# Schematic_Sensors.net
KiCad netlist of a schematic drawn in Altium Designer
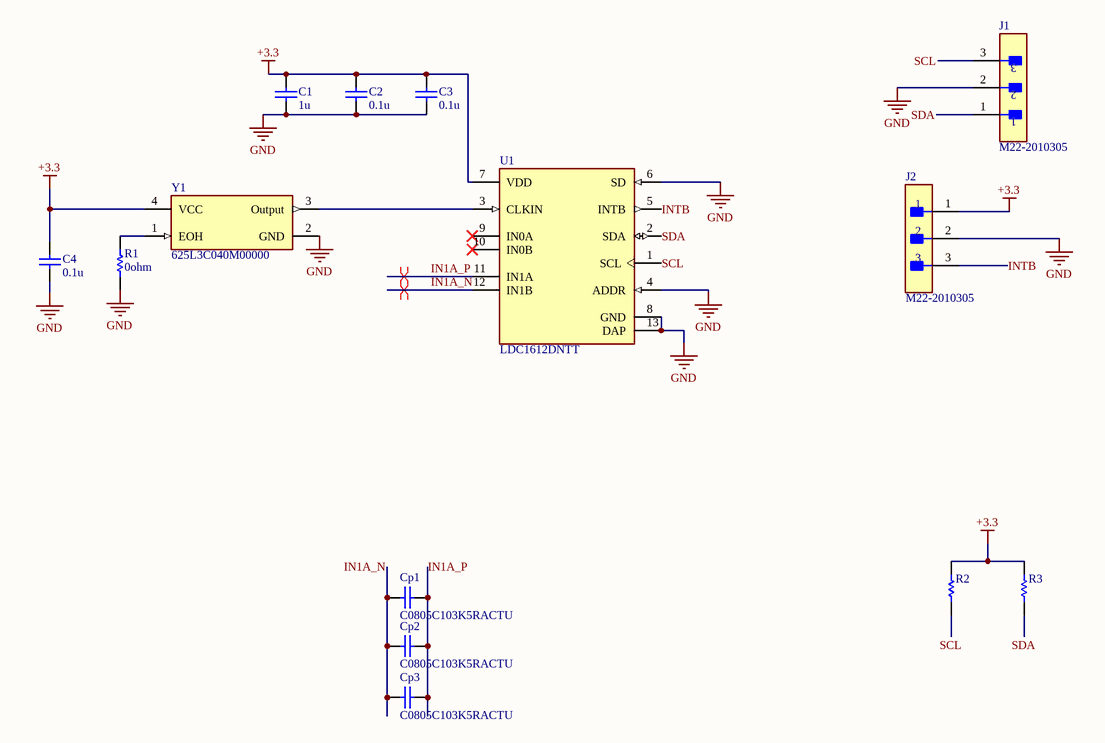
[diagram p0: Schematic_Sensors.SchDoc]

(export (version "E")
  (design (tool "Eeschema 10.0.6"))
  (components
    (comp (ref "C1")
      (value "1u")
      (footprint "CAPC1608X90X35ML10T15")
      (description "Chip Capacitor, 22 pF, +/- 5%, 50 V, -55 to 125 degC, 0603 (1608 Metric), RoHS, Tape and Reel")
      (fields (field (name "MANUFACTURER") "Murata"))
      (libsource (lib "Altium Content Vault") (part "CAP-NP-2"))
    )
    (comp (ref "C2")
      (value "0.1u")
      (footprint "CAPC1608X90X35ML10T15")
      (description "Chip Capacitor, 22 pF, +/- 5%, 50 V, -55 to 125 degC, 0603 (1608 Metric), RoHS, Tape and Reel")
      (fields (field (name "MANUFACTURER") "Murata"))
      (libsource (lib "Altium Content Vault") (part "CAP-NP-2"))
    )
    (comp (ref "C3")
      (value "0.1u")
      (footprint "CAPC1608X90X35ML10T15")
      (description "Chip Capacitor, 22 pF, +/- 5%, 50 V, -55 to 125 degC, 0603 (1608 Metric), RoHS, Tape and Reel")
      (fields (field (name "MANUFACTURER") "Murata"))
      (libsource (lib "Altium Content Vault") (part "CAP-NP-2"))
    )
    (comp (ref "C4")
      (value "0.1u")
      (footprint "CAPC1608X90X35ML10T15")
      (description "Chip Capacitor, 22 pF, +/- 5%, 50 V, -55 to 125 degC, 0603 (1608 Metric), RoHS, Tape and Reel")
      (fields (field (name "MANUFACTURER") "Murata"))
      (libsource (lib "Altium Content Vault") (part "CAP-NP-2"))
    )
    (comp (ref "Cp1")
      (value "C0805C103K5RACTU")
      (footprint "CAPC2013X88X50LL20T25")
      (fields (field (name "MANUFACTURER") "Kemet"))
      (libsource (lib "Altium Content Vault") (part "CAP"))
    )
    (comp (ref "Cp2")
      (value "C0805C103K5RACTU")
      (footprint "CAPC2013X88X50LL20T25")
      (fields (field (name "MANUFACTURER") "Kemet"))
      (libsource (lib "Altium Content Vault") (part "CAP"))
    )
    (comp (ref "Cp3")
      (value "C0805C103K5RACTU")
      (footprint "CAPC2013X88X50LL20T25")
      (fields (field (name "MANUFACTURER") "Kemet"))
      (libsource (lib "Altium Content Vault") (part "CAP"))
    )
    (comp (ref "J1")
      (value "M22-2010305")
      (footprint "FP-M22-2010305-MFG")
      (description "CONN HEADER VERT 3POS 2MM")
      (libsource (lib "") (part "d6a96a410146d2d686cfe982f2af7ec_1"))
    )
    (comp (ref "J2")
      (value "M22-2010305")
      (footprint "FP-M22-2010305-MFG")
      (description "CONN HEADER VERT 3POS 2MM")
      (libsource (lib "Altium Content Vault") (part "d6a96a410146d2d686cfe982f2af7ec"))
    )
    (comp (ref "R1")
      (value "0ohm")
      (footprint "RESC1608X55X25ML10T15")
      (description "Chip Resistor, 0 Ohm, +/- 5%, 0.1 W, -55 to 155 degC, 0603 (1608 Metric), RoHS, Tape and Reel")
      (fields (field (name "TOLERANCE") "5%") (field (name "MANUFACTURER") "Yageo"))
      (libsource (lib "Altium Content Vault") (part "RES-2"))
    )
    (comp (ref "R2")
      (value "CRCW060310K0FKEA")
      (footprint "RESC1609X50X30NL8T20")
      (description "Chip Resistor, 10 KOhm, +/- 1%, 100 mW, -55 to 155 degC, 0603 (1608 Metric), RoHS, Tape and Reel")
      (fields (field (name "MANUFACTURER") "Vishay Semiconductor"))
      (libsource (lib "Altium Content Vault") (part "RES-2"))
    )
    (comp (ref "R3")
      (value "CRCW060310K0FKEA")
      (footprint "RESC1609X50X30NL8T20")
      (description "Chip Resistor, 10 KOhm, +/- 1%, 100 mW, -55 to 155 degC, 0603 (1608 Metric), RoHS, Tape and Reel")
      (fields (field (name "MANUFACTURER") "Vishay Semiconductor"))
      (libsource (lib "Altium Content Vault") (part "RES-2"))
    )
    (comp (ref "U1")
      (value "LDC1612DNTT")
      (footprint "FP-DNT0012B-MFG")
      (description "IC IND TO DGTL 28BIT 1K 12WSON")
      (libsource (lib "Altium Content Vault") (part "d15d1dde6957b5eef4a1a46d84eb5d6"))
    )
    (comp (ref "Y1")
      (value "625L3C040M00000")
      (footprint "FP-625-MFG")
      (description "XTAL OSC XO 40.0000MHZ CMOS SMD")
      (libsource (lib "Altium Content Vault") (part "9c3e14d6329513fa8fa4cc4a840e5d2"))
    )
  )
  (nets
    (net (code "1") (name "+3.3") (class "Default")
      (node (ref "C1") (pin "2") (pinfunction "2_2") (pintype "passive"))
      (node (ref "C2") (pin "2") (pinfunction "2_2") (pintype "passive"))
      (node (ref "C3") (pin "2") (pinfunction "2_2") (pintype "passive"))
      (node (ref "C4") (pin "2") (pinfunction "2_2") (pintype "passive"))
      (node (ref "J2") (pin "1") (pinfunction "1_1") (pintype "passive"))
      (node (ref "R2") (pin "2") (pinfunction "2_2") (pintype "passive"))
      (node (ref "R3") (pin "2") (pinfunction "2_2") (pintype "passive"))
      (node (ref "U1") (pin "7") (pinfunction "VDD_7") (pintype "power_in"))
      (node (ref "Y1") (pin "4") (pinfunction "VCC_4") (pintype "power_in"))
    )
    (net (code "2") (name "/IN1A_N") (class "Default")
      (node (ref "Cp1") (pin "1") (pinfunction "1_1") (pintype "passive"))
      (node (ref "Cp2") (pin "1") (pinfunction "1_1") (pintype "passive"))
      (node (ref "Cp3") (pin "1") (pinfunction "1_1") (pintype "passive"))
      (node (ref "U1") (pin "12") (pinfunction "IN1B_12") (pintype "passive"))
    )
    (net (code "3") (name "/IN1A_P") (class "Default")
      (node (ref "Cp1") (pin "2") (pinfunction "2_2") (pintype "passive"))
      (node (ref "Cp2") (pin "2") (pinfunction "2_2") (pintype "passive"))
      (node (ref "Cp3") (pin "2") (pinfunction "2_2") (pintype "passive"))
      (node (ref "U1") (pin "11") (pinfunction "IN1A_11") (pintype "passive"))
    )
    (net (code "4") (name "/INTB") (class "Default")
      (node (ref "J2") (pin "3") (pinfunction "3_3") (pintype "passive"))
      (node (ref "U1") (pin "5") (pinfunction "INTB_5") (pintype "output"))
    )
    (net (code "5") (name "/SCL") (class "Default")
      (node (ref "J1") (pin "3") (pinfunction "3_3") (pintype "passive"))
      (node (ref "R2") (pin "1") (pinfunction "1_1") (pintype "passive"))
      (node (ref "U1") (pin "1") (pinfunction "SCL_1") (pintype "passive"))
    )
    (net (code "6") (name "/SDA") (class "Default")
      (node (ref "J1") (pin "1") (pinfunction "1_1") (pintype "passive"))
      (node (ref "R3") (pin "1") (pinfunction "1_1") (pintype "passive"))
      (node (ref "U1") (pin "2") (pinfunction "SDA_2") (pintype "bidirectional"))
    )
    (net (code "7") (name "GND") (class "Default")
      (node (ref "C1") (pin "1") (pinfunction "1_1") (pintype "passive"))
      (node (ref "C2") (pin "1") (pinfunction "1_1") (pintype "passive"))
      (node (ref "C3") (pin "1") (pinfunction "1_1") (pintype "passive"))
      (node (ref "C4") (pin "1") (pinfunction "1_1") (pintype "passive"))
      (node (ref "J1") (pin "2") (pinfunction "2_2") (pintype "passive"))
      (node (ref "J2") (pin "2") (pinfunction "2_2") (pintype "passive"))
      (node (ref "R1") (pin "1") (pinfunction "1_1") (pintype "passive"))
      (node (ref "U1") (pin "13") (pinfunction "DAP_13") (pintype "power_in"))
      (node (ref "U1") (pin "4") (pinfunction "ADDR_4") (pintype "input"))
      (node (ref "U1") (pin "6") (pinfunction "SD_6") (pintype "input"))
      (node (ref "U1") (pin "8") (pinfunction "GND_8") (pintype "power_in"))
      (node (ref "Y1") (pin "2") (pinfunction "GND_2") (pintype "power_in"))
    )
    (net (code "8") (name "Net-(U1-CLKIN)") (class "Default")
      (node (ref "U1") (pin "3") (pinfunction "CLKIN_3") (pintype "input"))
      (node (ref "Y1") (pin "3") (pinfunction "Output_3") (pintype "output"))
    )
    (net (code "9") (name "Net-(Y1-EOH)") (class "Default")
      (node (ref "R1") (pin "2") (pinfunction "2_2") (pintype "passive"))
      (node (ref "Y1") (pin "1") (pinfunction "EOH_1") (pintype "input"))
    )
    (net (code "10") (name "unconnected-(U1-IN0A-Pad9)") (class "Default")
      (node (ref "U1") (pin "9") (pinfunction "IN0A_9") (pintype "passive+no_connect"))
    )
    (net (code "11") (name "unconnected-(U1-IN0B-Pad10)") (class "Default")
      (node (ref "U1") (pin "10") (pinfunction "IN0B_10") (pintype "passive+no_connect"))
    )
  )
)
